# Sheet1.net
KiCad netlist of a schematic drawn in Altium Designer
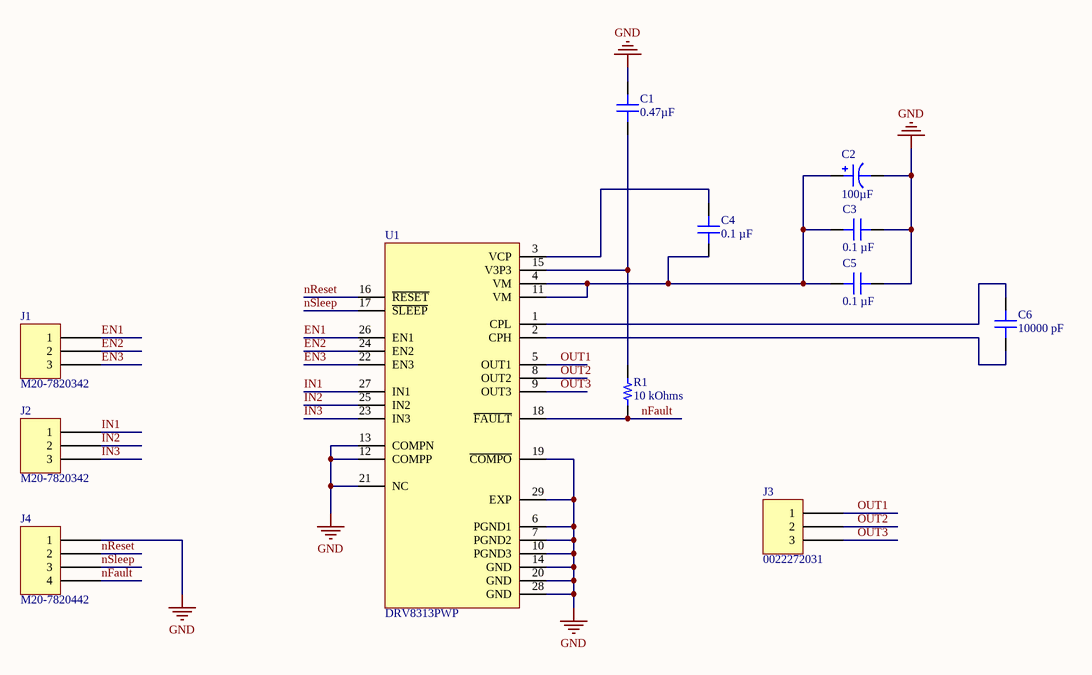
[diagram p0: Sheet1.SchDoc]

(export (version "E")
  (design (tool "Eeschema 10.0.6"))
  (components
    (comp (ref "C1")
      (value "0.47µF")
      (footprint "CAP 0805_2012")
      (description "CAP CER 0.47UF 25V X7R 0805")
      (fields (field (name "PART NUMBER") "MM053C474KCZ2A") (field (name "MANUFACTURER") "AVX Corporation"))
      (libsource (lib "Celestial Altium Library - altium_library") (part "Capacitor"))
    )
    (comp (ref "C2")
      (value "100µF")
      (footprint "CAP TH ALUM ELEC D10.00mm S5.00mm H12.50mm")
      (description "CAP ALUM 100UF 20% 50V RADIAL")
      (fields
        (field (name "PART NUMBER") "EEU-FC1H101")
        (field (name "MANUFACTURER") "Panasonic Electronic Components")
      )
      (libsource (lib "Celestial Altium Library - altium_library") (part "Polarised Capacitor"))
    )
    (comp (ref "C3")
      (value "0.1 µF")
      (footprint "CAP 0805_2012")
      (description "CAP CER 0.1UF 25V X7R 0805")
      (fields
        (field (name "PART NUMBER") "0805B104K250CT")
        (field (name "MANUFACTURER") "Walsin Technology Corporation")
      )
      (libsource (lib "Celestial Altium Library - altium_library") (part "Capacitor"))
    )
    (comp (ref "C4")
      (value "0.1 µF")
      (footprint "CAP 0805_2012")
      (description "CAP CER 0.1UF 25V X7R 0805")
      (fields
        (field (name "PART NUMBER") "0805B104K250CT")
        (field (name "MANUFACTURER") "Walsin Technology Corporation")
      )
      (libsource (lib "Celestial Altium Library - altium_library") (part "Capacitor"))
    )
    (comp (ref "C5")
      (value "0.1 µF")
      (footprint "CAP 0805_2012")
      (description "CAP CER 0.1UF 25V X7R 0805")
      (fields
        (field (name "PART NUMBER") "0805B104K250CT")
        (field (name "MANUFACTURER") "Walsin Technology Corporation")
      )
      (libsource (lib "Celestial Altium Library - altium_library") (part "Capacitor"))
    )
    (comp (ref "C6")
      (value "10000 pF")
      (footprint "CAP 0805_2012")
      (description "CAP CER 0805 10NF 25V C0G 5%")
      (fields (field (name "PART NUMBER") "C0805C103J3GECAUTO") (field (name "MANUFACTURER") "KEMET"))
      (libsource (lib "Celestial Altium Library - altium_library") (part "Capacitor"))
    )
    (comp (ref "J1")
      (value "M20-7820342")
      (footprint "HARWIN M20-7820345")
      (description "CONN RCPT 3POS 0.1 GOLD PCB")
      (fields (field (name "MANUFACTURER") "Harwin Inc."))
      (libsource (lib "Celestial Altium Library - altium_library") (part "3 Pin"))
    )
    (comp (ref "J2")
      (value "M20-7820342")
      (footprint "HARWIN M20-7820345")
      (description "CONN RCPT 3POS 0.1 GOLD PCB")
      (fields (field (name "MANUFACTURER") "Harwin Inc."))
      (libsource (lib "Celestial Altium Library - altium_library") (part "3 Pin"))
    )
    (comp (ref "J3")
      (value "0022272031")
      (footprint "MOLEX KK 0022272031")
      (description "CONN HEADER VERT 3POS 2.54MM")
      (fields (field (name "MANUFACTURER") "Molex"))
      (libsource (lib "Celestial Altium Library - altium_library") (part "3 Pin"))
    )
    (comp (ref "J4")
      (value "M20-7820442")
      (footprint "HARWIN M20-7820445")
      (description "CONN RCPT 4POS 0.1 GOLD PCB")
      (fields (field (name "MANUFACTURER") "Harwin Inc."))
      (libsource (lib "Celestial Altium Library - altium_library") (part "4 Pin"))
    )
    (comp (ref "R1")
      (value "10 kOhms")
      (footprint "RES 0805_2012")
      (description "RES 10K OHM 1% 1/4W 0805")
      (fields
        (field (name "PART NUMBER") "RNCP0805FTD10K0")
        (field (name "MANUFACTURER") "Stackpole Electronics Inc")
      )
      (libsource (lib "Celestial Altium Library - altium_library") (part "Resistor"))
    )
    (comp (ref "U1")
      (value "DRV8313PWP")
      (footprint "DRV8313")
      (description "Motor Driver Power MOSFET Parallel 28-HTSSOP")
      (fields
        (field (name "MANUFACTURER") "Texas Instruments")
        (field (name "MANUFACTURER PART NUMBER") "DRV8313PWPR")
      )
      (libsource (lib "Schlib1") (part "DRV8313PWP"))
    )
  )
  (nets
    (net (code "1") (name "/EN1") (class "Default")
      (node (ref "J1") (pin "1") (pinfunction "1_1") (pintype "passive"))
      (node (ref "U1") (pin "26") (pinfunction "EN1_26") (pintype "open_collector"))
    )
    (net (code "2") (name "/EN2") (class "Default")
      (node (ref "J1") (pin "2") (pinfunction "2_2") (pintype "passive"))
      (node (ref "U1") (pin "24") (pinfunction "EN2_24") (pintype "open_collector"))
    )
    (net (code "3") (name "/EN3") (class "Default")
      (node (ref "J1") (pin "3") (pinfunction "3_3") (pintype "passive"))
      (node (ref "U1") (pin "22") (pinfunction "EN3_22") (pintype "open_collector"))
    )
    (net (code "4") (name "/IN1") (class "Default")
      (node (ref "J2") (pin "1") (pinfunction "1_1") (pintype "passive"))
      (node (ref "U1") (pin "27") (pinfunction "IN1_27") (pintype "open_collector"))
    )
    (net (code "5") (name "/IN2") (class "Default")
      (node (ref "J2") (pin "2") (pinfunction "2_2") (pintype "passive"))
      (node (ref "U1") (pin "25") (pinfunction "IN2_25") (pintype "open_collector"))
    )
    (net (code "6") (name "/IN3") (class "Default")
      (node (ref "J2") (pin "3") (pinfunction "3_3") (pintype "passive"))
      (node (ref "U1") (pin "23") (pinfunction "IN3_23") (pintype "open_collector"))
    )
    (net (code "7") (name "/OUT1") (class "Default")
      (node (ref "J3") (pin "1") (pinfunction "1_1") (pintype "passive"))
      (node (ref "U1") (pin "5") (pinfunction "OUT1_5") (pintype "open_collector"))
    )
    (net (code "8") (name "/OUT2") (class "Default")
      (node (ref "J3") (pin "2") (pinfunction "2_2") (pintype "passive"))
      (node (ref "U1") (pin "8") (pinfunction "OUT2_8") (pintype "open_collector"))
    )
    (net (code "9") (name "/OUT3") (class "Default")
      (node (ref "J3") (pin "3") (pinfunction "3_3") (pintype "passive"))
      (node (ref "U1") (pin "9") (pinfunction "OUT3_9") (pintype "open_collector"))
    )
    (net (code "10") (name "/nFault") (class "Default")
      (node (ref "J4") (pin "4") (pinfunction "4_4") (pintype "passive"))
      (node (ref "R1") (pin "2") (pinfunction "2_2") (pintype "passive"))
      (node (ref "U1") (pin "18") (pinfunction "~{FAULT}_18") (pintype "open_collector"))
    )
    (net (code "11") (name "/nReset") (class "Default")
      (node (ref "J4") (pin "2") (pinfunction "2_2") (pintype "passive"))
      (node (ref "U1") (pin "16") (pinfunction "~{RESET}_16") (pintype "open_collector"))
    )
    (net (code "12") (name "/nSleep") (class "Default")
      (node (ref "J4") (pin "3") (pinfunction "3_3") (pintype "passive"))
      (node (ref "U1") (pin "17") (pinfunction "~{SLEEP}_17") (pintype "open_collector"))
    )
    (net (code "13") (name "GND") (class "Default")
      (node (ref "C1") (pin "2") (pinfunction "2_2") (pintype "passive"))
      (node (ref "C2") (pin "2") (pinfunction "2_2") (pintype "passive"))
      (node (ref "C3") (pin "2") (pinfunction "2_2") (pintype "passive"))
      (node (ref "C5") (pin "2") (pinfunction "2_2") (pintype "passive"))
      (node (ref "J4") (pin "1") (pinfunction "1_1") (pintype "passive"))
      (node (ref "U1") (pin "10") (pinfunction "PGND3_10") (pintype "open_collector"))
      (node (ref "U1") (pin "12") (pinfunction "COMPP_12") (pintype "open_collector"))
      (node (ref "U1") (pin "13") (pinfunction "COMPN_13") (pintype "open_collector"))
      (node (ref "U1") (pin "14") (pinfunction "GND_14") (pintype "open_collector"))
      (node (ref "U1") (pin "19") (pinfunction "~{COMPO}_19") (pintype "open_collector"))
      (node (ref "U1") (pin "20") (pinfunction "GND_20") (pintype "open_collector"))
      (node (ref "U1") (pin "21") (pinfunction "NC_21") (pintype "open_collector"))
      (node (ref "U1") (pin "28") (pinfunction "GND_28") (pintype "open_collector"))
      (node (ref "U1") (pin "29") (pinfunction "EXP_29") (pintype "open_collector"))
      (node (ref "U1") (pin "6") (pinfunction "PGND1_6") (pintype "open_collector"))
      (node (ref "U1") (pin "7") (pinfunction "PGND2_7") (pintype "open_collector"))
    )
    (net (code "14") (name "Net-(C2-Pad1)") (class "Default")
      (node (ref "C2") (pin "1") (pinfunction "1_1") (pintype "passive"))
      (node (ref "C3") (pin "1") (pinfunction "1_1") (pintype "passive"))
      (node (ref "C4") (pin "1") (pinfunction "1_1") (pintype "passive"))
      (node (ref "C5") (pin "1") (pinfunction "1_1") (pintype "passive"))
      (node (ref "U1") (pin "11") (pinfunction "VM_11") (pintype "open_collector"))
      (node (ref "U1") (pin "4") (pinfunction "VM_4") (pintype "open_collector"))
    )
    (net (code "15") (name "Net-(U1-CPH)") (class "Default")
      (node (ref "C6") (pin "1") (pinfunction "1_1") (pintype "passive"))
      (node (ref "U1") (pin "2") (pinfunction "CPH_2") (pintype "open_collector"))
    )
    (net (code "16") (name "Net-(U1-CPL)") (class "Default")
      (node (ref "C6") (pin "2") (pinfunction "2_2") (pintype "passive"))
      (node (ref "U1") (pin "1") (pinfunction "CPL_1") (pintype "open_collector"))
    )
    (net (code "17") (name "Net-(U1-V3P3)") (class "Default")
      (node (ref "C1") (pin "1") (pinfunction "1_1") (pintype "passive"))
      (node (ref "R1") (pin "1") (pinfunction "1_1") (pintype "passive"))
      (node (ref "U1") (pin "15") (pinfunction "V3P3_15") (pintype "open_collector"))
    )
    (net (code "18") (name "Net-(U1-VCP)") (class "Default")
      (node (ref "C4") (pin "2") (pinfunction "2_2") (pintype "passive"))
      (node (ref "U1") (pin "3") (pinfunction "VCP_3") (pintype "open_collector"))
    )
  )
)
